# SparkFun_9DoF_ISM330DLC-MMC5983MA.net
KiCad netlist of a schematic drawn in EAGLE
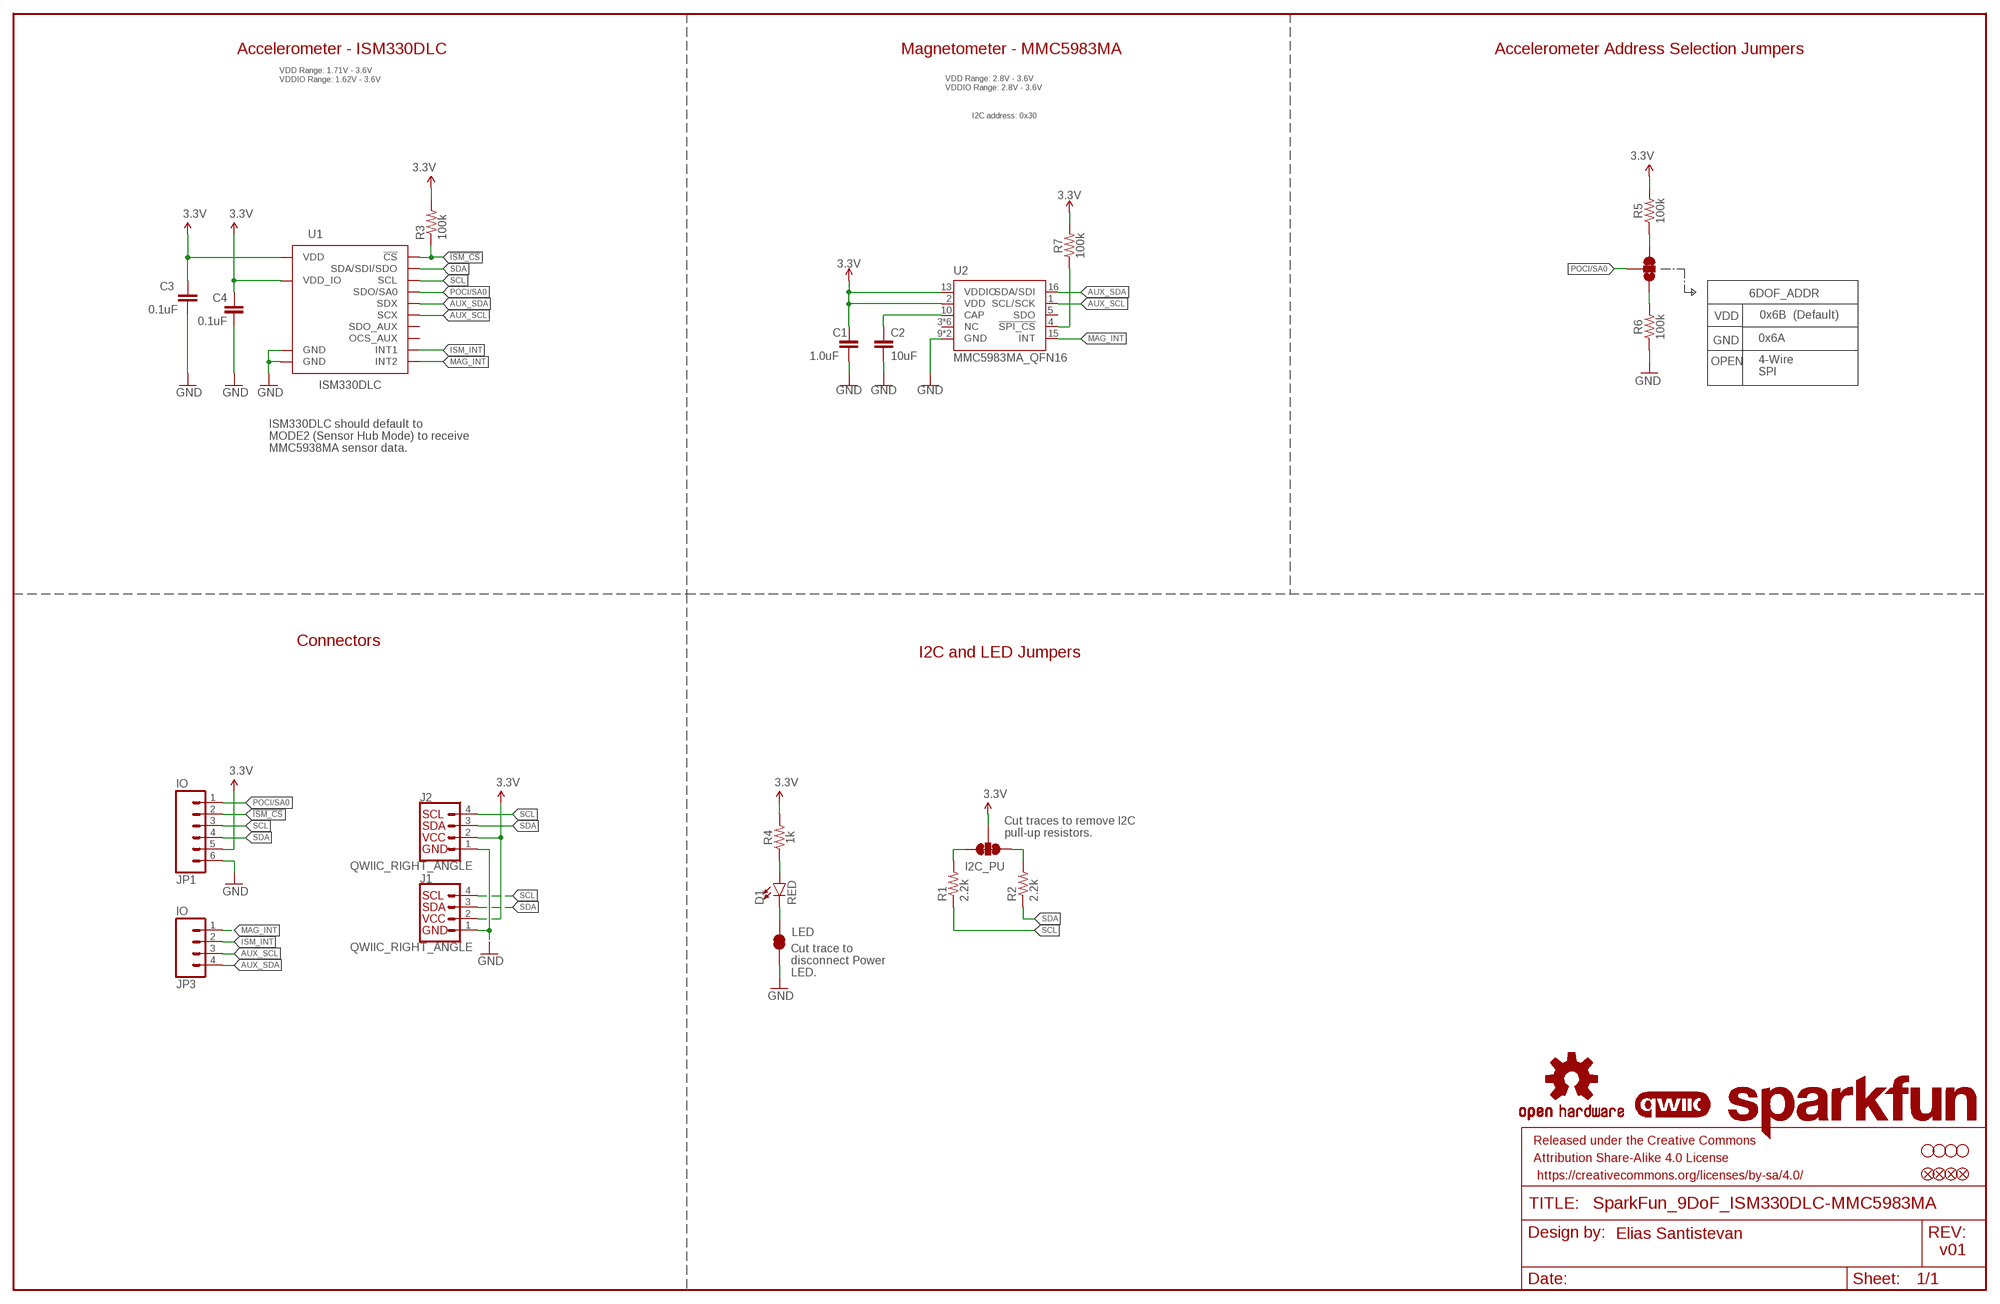
[diagram p0: schematic, sheet 1]

(export (version "E")
  (design (tool "Eeschema 10.0.6"))
  (components
    (comp (ref "6DOF_ADDR")
      (value "JUMPER-SMT_3_1-NC_TRACE_SILK")
      (footprint "eagle-import:SMT-JUMPER_3_1-NC_TRACE_SILK")
      (libsource (lib "eagle-import") (part "JUMPER-SMT_3_1-NC_TRACE_SILK"))
    )
    (comp (ref "C1")
      (value "1.0uF")
      (footprint "eagle-import:0603")
      (libsource (lib "eagle-import") (part "1.0UF-0603-16V-10%"))
    )
    (comp (ref "C2")
      (value "10uF")
      (footprint "eagle-import:0603")
      (libsource (lib "eagle-import") (part "10UF-0603-6.3V-20%"))
    )
    (comp (ref "C3")
      (value "0.1uF")
      (footprint "eagle-import:0603")
      (libsource (lib "eagle-import") (part "0.1UF-0603-25V-(+80/-20%)"))
    )
    (comp (ref "C4")
      (value "0.1uF")
      (footprint "eagle-import:0603")
      (libsource (lib "eagle-import") (part "0.1UF-0603-25V-(+80/-20%)"))
    )
    (comp (ref "D1")
      (value "RED")
      (footprint "eagle-import:LED-0603")
      (libsource (lib "eagle-import") (part "LED-RED0603"))
    )
    (comp (ref "FD1")
      (value "FIDUCIALUFIDUCIAL")
      (footprint "eagle-import:FIDUCIAL-MICRO")
      (libsource (lib "eagle-import") (part "FIDUCIALUFIDUCIAL"))
    )
    (comp (ref "FD2")
      (value "FIDUCIALUFIDUCIAL")
      (footprint "eagle-import:FIDUCIAL-MICRO")
      (libsource (lib "eagle-import") (part "FIDUCIALUFIDUCIAL"))
    )
    (comp (ref "FID1")
      (value "FIDUCIALUFIDUCIAL")
      (footprint "eagle-import:FIDUCIAL-MICRO")
      (libsource (lib "eagle-import") (part "FIDUCIALUFIDUCIAL"))
    )
    (comp (ref "FID2")
      (value "FIDUCIALUFIDUCIAL")
      (footprint "eagle-import:FIDUCIAL-MICRO")
      (libsource (lib "eagle-import") (part "FIDUCIALUFIDUCIAL"))
    )
    (comp (ref "FRAME2")
      (value "FRAME-LEDGER")
      (footprint "eagle-import:CREATIVE_COMMONS")
      (libsource (lib "eagle-import") (part "FRAME-LEDGER"))
    )
    (comp (ref "I2C_PU")
      (value "S_MODE")
      (footprint "eagle-import:SMT-JUMPER_3_2-NC_TRACE_SILK")
      (libsource (lib "eagle-import") (part "JUMPER-SMT_3_2-NC_TRACE_SILK"))
    )
    (comp (ref "J1")
      (value "QWIIC_RIGHT_ANGLE")
      (footprint "eagle-import:JST04_1MM_RA")
      (libsource (lib "eagle-import") (part "QWIIC_CONNECTORJS-1MM"))
    )
    (comp (ref "J2")
      (value "QWIIC_RIGHT_ANGLE")
      (footprint "eagle-import:JST04_1MM_RA")
      (libsource (lib "eagle-import") (part "QWIIC_CONNECTORJS-1MM"))
    )
    (comp (ref "JP1")
      (value "IO")
      (footprint "eagle-import:1X06_NO_SILK")
      (libsource (lib "eagle-import") (part "CONN_06NO_SILK_NO_POP"))
    )
    (comp (ref "JP3")
      (value "IO")
      (footprint "eagle-import:1X04_NO_SILK")
      (libsource (lib "eagle-import") (part "CONN_041X04_NO_SILK_NO_POP"))
    )
    (comp (ref "LED")
      (value "JUMPER-SMT_2_NC_TRACE_SILK")
      (footprint "eagle-import:SMT-JUMPER_2_NC_TRACE_SILK")
      (libsource (lib "eagle-import") (part "JUMPER-SMT_2_NC_TRACE_SILK"))
    )
    (comp (ref "LOGO1")
      (value "QWIIC_LOGO_4MM")
      (footprint "eagle-import:QWIIC_4MM")
      (libsource (lib "eagle-import") (part "QWIIC_LOGO_4MM"))
    )
    (comp (ref "LOGO2")
      (value "OSHW-LOGOMINI")
      (footprint "eagle-import:OSHW-LOGO-MINI")
      (libsource (lib "eagle-import") (part "OSHW-LOGOMINI"))
    )
    (comp (ref "LOGO3")
      (value "SFE_LOGO_NAME.1_INCH")
      (footprint "eagle-import:SFE_LOGO_NAME_.1")
      (libsource (lib "eagle-import") (part "SFE_LOGO_NAME.1_INCH"))
    )
    (comp (ref "R1")
      (value "2.2k")
      (footprint "eagle-import:0603")
      (libsource (lib "eagle-import") (part "2.2KOHM-0603-1/10W-1%"))
    )
    (comp (ref "R2")
      (value "2.2k")
      (footprint "eagle-import:0603")
      (libsource (lib "eagle-import") (part "2.2KOHM-0603-1/10W-1%"))
    )
    (comp (ref "R3")
      (value "100k")
      (footprint "eagle-import:0603")
      (libsource (lib "eagle-import") (part "100KOHM-0603-1/10W-1%"))
    )
    (comp (ref "R4")
      (value "1k")
      (footprint "eagle-import:0603")
      (libsource (lib "eagle-import") (part "1KOHM-0603-1/10W-1%"))
    )
    (comp (ref "R5")
      (value "100k")
      (footprint "eagle-import:0603")
      (libsource (lib "eagle-import") (part "100KOHM-0603-1/10W-1%"))
    )
    (comp (ref "R6")
      (value "100k")
      (footprint "eagle-import:0603")
      (libsource (lib "eagle-import") (part "100KOHM-0603-1/10W-1%"))
    )
    (comp (ref "R7")
      (value "100k")
      (footprint "eagle-import:0603")
      (libsource (lib "eagle-import") (part "100KOHM-0603-1/10W-1%"))
    )
    (comp (ref "STANDOFF1")
      (value "STAND-OFFTIGHT")
      (footprint "eagle-import:STAND-OFF-TIGHT")
      (libsource (lib "eagle-import") (part "STAND-OFFTIGHT"))
    )
    (comp (ref "STANDOFF2")
      (value "STAND-OFFTIGHT")
      (footprint "eagle-import:STAND-OFF-TIGHT")
      (libsource (lib "eagle-import") (part "STAND-OFFTIGHT"))
    )
    (comp (ref "STANDOFF3")
      (value "STAND-OFFTIGHT")
      (footprint "eagle-import:STAND-OFF-TIGHT")
      (libsource (lib "eagle-import") (part "STAND-OFFTIGHT"))
    )
    (comp (ref "STANDOFF4")
      (value "STAND-OFFTIGHT")
      (footprint "eagle-import:STAND-OFF-TIGHT")
      (libsource (lib "eagle-import") (part "STAND-OFFTIGHT"))
    )
    (comp (ref "U1")
      (value "ISM330DLC")
      (footprint "eagle-import:LGA-14L")
      (libsource (lib "eagle-import") (part "ISM330DLC"))
    )
    (comp (ref "U2")
      (value "MMC5983MA_QFN16")
      (footprint "eagle-import:LGA-16-3X3MM-4X4PINS")
      (libsource (lib "eagle-import") (part "MMC5983MA_QFN16"))
    )
  )
  (nets
    (net (code "1") (name "/~{ISM_CS}") (class "Default")
      (node (ref "JP1") (pin "2") (pinfunction "2_2") (pintype "passive"))
      (node (ref "R3") (pin "1") (pinfunction "1_1") (pintype "passive"))
      (node (ref "U1") (pin "P12") (pinfunction "~{CS}_P12") (pintype "bidirectional"))
    )
    (net (code "2") (name "3.3V") (class "Default")
      (node (ref "C1") (pin "1") (pinfunction "1_1") (pintype "passive"))
      (node (ref "C3") (pin "1") (pinfunction "1_1") (pintype "passive"))
      (node (ref "C4") (pin "1") (pinfunction "1_1") (pintype "passive"))
      (node (ref "I2C_PU") (pin "2") (pinfunction "2_2") (pintype "passive"))
      (node (ref "J1") (pin "2") (pinfunction "2_2") (pintype "power_in"))
      (node (ref "J2") (pin "2") (pinfunction "2_2") (pintype "power_in"))
      (node (ref "JP1") (pin "5") (pinfunction "5_5") (pintype "passive"))
      (node (ref "R3") (pin "2") (pinfunction "2_2") (pintype "passive"))
      (node (ref "R4") (pin "2") (pinfunction "2_2") (pintype "passive"))
      (node (ref "R5") (pin "2") (pinfunction "2_2") (pintype "passive"))
      (node (ref "R7") (pin "2") (pinfunction "2_2") (pintype "passive"))
      (node (ref "U1") (pin "P5") (pinfunction "VDD_IO_P5") (pintype "power_in"))
      (node (ref "U1") (pin "P8") (pinfunction "VDD_P8") (pintype "power_in"))
      (node (ref "U2") (pin "13") (pinfunction "VDDIO_13") (pintype "power_in"))
      (node (ref "U2") (pin "2") (pinfunction "VDD_2") (pintype "power_in"))
    )
    (net (code "3") (name "AUX_SCL") (class "Default")
      (node (ref "JP3") (pin "3") (pinfunction "3_3") (pintype "passive"))
      (node (ref "U1") (pin "P3") (pinfunction "SCX_P3") (pintype "bidirectional"))
      (node (ref "U2") (pin "1") (pinfunction "SCL/SCK_1") (pintype "bidirectional"))
    )
    (net (code "4") (name "AUX_SDA") (class "Default")
      (node (ref "JP3") (pin "4") (pinfunction "4_4") (pintype "passive"))
      (node (ref "U1") (pin "P2") (pinfunction "SDX_P2") (pintype "bidirectional"))
      (node (ref "U2") (pin "16") (pinfunction "SDA/SDI_16") (pintype "bidirectional"))
    )
    (net (code "5") (name "GND") (class "Default")
      (node (ref "C1") (pin "2") (pinfunction "2_2") (pintype "passive"))
      (node (ref "C2") (pin "2") (pinfunction "2_2") (pintype "passive"))
      (node (ref "C3") (pin "2") (pinfunction "2_2") (pintype "passive"))
      (node (ref "C4") (pin "2") (pinfunction "2_2") (pintype "passive"))
      (node (ref "J1") (pin "1") (pinfunction "1_1") (pintype "power_in"))
      (node (ref "J2") (pin "1") (pinfunction "1_1") (pintype "power_in"))
      (node (ref "JP1") (pin "6") (pinfunction "6_6") (pintype "passive"))
      (node (ref "LED") (pin "1") (pinfunction "1_1") (pintype "passive"))
      (node (ref "R6") (pin "1") (pinfunction "1_1") (pintype "passive"))
      (node (ref "U1") (pin "P6") (pinfunction "GND_P6") (pintype "power_in"))
      (node (ref "U1") (pin "P7") (pinfunction "GND_P7") (pintype "power_in"))
      (node (ref "U2") (pin "11") (pinfunction "GND_11") (pintype "power_in"))
      (node (ref "U2") (pin "9") (pinfunction "GND_9") (pintype "power_in"))
    )
    (net (code "6") (name "ISM_INT") (class "Default")
      (node (ref "JP3") (pin "2") (pinfunction "2_2") (pintype "passive"))
      (node (ref "U1") (pin "P4") (pinfunction "INT1_P4") (pintype "bidirectional"))
    )
    (net (code "7") (name "MAG_INT") (class "Default")
      (node (ref "JP3") (pin "1") (pinfunction "1_1") (pintype "passive"))
      (node (ref "U1") (pin "P9") (pinfunction "INT2_P9") (pintype "bidirectional"))
      (node (ref "U2") (pin "15") (pinfunction "INT_15") (pintype "output"))
    )
    (net (code "8") (name "Net-(6DOF_ADDR-Pad1)") (class "Default")
      (node (ref "6DOF_ADDR") (pin "1") (pinfunction "1_1") (pintype "passive"))
      (node (ref "R6") (pin "2") (pinfunction "2_2") (pintype "passive"))
    )
    (net (code "9") (name "Net-(6DOF_ADDR-Pad3)") (class "Default")
      (node (ref "6DOF_ADDR") (pin "3") (pinfunction "3_3") (pintype "passive"))
      (node (ref "R5") (pin "1") (pinfunction "1_1") (pintype "passive"))
    )
    (net (code "10") (name "Net-(D1-PadA)") (class "Default")
      (node (ref "D1") (pin "A") (pinfunction "A_A") (pintype "passive"))
      (node (ref "R4") (pin "1") (pinfunction "1_1") (pintype "passive"))
    )
    (net (code "11") (name "Net-(D1-PadC)") (class "Default")
      (node (ref "D1") (pin "C") (pinfunction "C_C") (pintype "passive"))
      (node (ref "LED") (pin "2") (pinfunction "2_2") (pintype "passive"))
    )
    (net (code "12") (name "Net-(I2C_PU-Pad1)") (class "Default")
      (node (ref "I2C_PU") (pin "1") (pinfunction "1_1") (pintype "passive"))
      (node (ref "R1") (pin "2") (pinfunction "2_2") (pintype "passive"))
    )
    (net (code "13") (name "Net-(I2C_PU-Pad3)") (class "Default")
      (node (ref "I2C_PU") (pin "3") (pinfunction "3_3") (pintype "passive"))
      (node (ref "R2") (pin "2") (pinfunction "2_2") (pintype "passive"))
    )
    (net (code "14") (name "Net-(U2-CAP)") (class "Default")
      (node (ref "C2") (pin "1") (pinfunction "1_1") (pintype "passive"))
      (node (ref "U2") (pin "10") (pinfunction "CAP_10") (pintype "passive"))
    )
    (net (code "15") (name "Net-(U2-~{SPI_CS})") (class "Default")
      (node (ref "R7") (pin "1") (pinfunction "1_1") (pintype "passive"))
      (node (ref "U2") (pin "4") (pinfunction "~{SPI_CS}_4") (pintype "input"))
    )
    (net (code "16") (name "POCI{slash}SA0") (class "Default")
      (node (ref "6DOF_ADDR") (pin "2") (pinfunction "2_2") (pintype "passive"))
      (node (ref "JP1") (pin "1") (pinfunction "1_1") (pintype "passive"))
      (node (ref "U1") (pin "P1") (pinfunction "SDO/SA0_P1") (pintype "bidirectional"))
    )
    (net (code "17") (name "SCL") (class "Default")
      (node (ref "J1") (pin "4") (pinfunction "4_4") (pintype "passive"))
      (node (ref "J2") (pin "4") (pinfunction "4_4") (pintype "passive"))
      (node (ref "JP1") (pin "3") (pinfunction "3_3") (pintype "passive"))
      (node (ref "R1") (pin "1") (pinfunction "1_1") (pintype "passive"))
      (node (ref "U1") (pin "P13") (pinfunction "SCL_P13") (pintype "bidirectional"))
    )
    (net (code "18") (name "SDA") (class "Default")
      (node (ref "J1") (pin "3") (pinfunction "3_3") (pintype "passive"))
      (node (ref "J2") (pin "3") (pinfunction "3_3") (pintype "passive"))
      (node (ref "JP1") (pin "4") (pinfunction "4_4") (pintype "passive"))
      (node (ref "R2") (pin "1") (pinfunction "1_1") (pintype "passive"))
      (node (ref "U1") (pin "P14") (pinfunction "SDA/SDI/SDO_P14") (pintype "bidirectional"))
    )
    (net (code "19") (name "unconnected-(U1-OCS_AUX-PadP10)") (class "Default")
      (node (ref "U1") (pin "P10") (pinfunction "OCS_AUX_P10") (pintype "bidirectional"))
    )
    (net (code "20") (name "unconnected-(U1-SDO_AUX-PadP11)") (class "Default")
      (node (ref "U1") (pin "P11") (pinfunction "SDO_AUX_P11") (pintype "bidirectional"))
    )
    (net (code "21") (name "unconnected-(U2-NC-Pad3)") (class "Default")
      (node (ref "U2") (pin "3") (pinfunction "NC_3") (pintype "no_connect"))
    )
    (net (code "22") (name "unconnected-(U2-NC-Pad6)") (class "Default")
      (node (ref "U2") (pin "6") (pinfunction "NC_6") (pintype "no_connect"))
    )
    (net (code "23") (name "unconnected-(U2-NC-Pad7)") (class "Default")
      (node (ref "U2") (pin "7") (pinfunction "NC_7") (pintype "no_connect"))
    )
    (net (code "24") (name "unconnected-(U2-NC-Pad8)") (class "Default")
      (node (ref "U2") (pin "8") (pinfunction "NC_8") (pintype "no_connect"))
    )
    (net (code "25") (name "unconnected-(U2-NC-Pad12)") (class "Default")
      (node (ref "U2") (pin "12") (pinfunction "NC_12") (pintype "no_connect"))
    )
    (net (code "26") (name "unconnected-(U2-NC-Pad14)") (class "Default")
      (node (ref "U2") (pin "14") (pinfunction "NC_14") (pintype "no_connect"))
    )
    (net (code "27") (name "unconnected-(U2-SDO-Pad5)") (class "Default")
      (node (ref "U2") (pin "5") (pinfunction "SDO_5") (pintype "output"))
    )
  )
)
